# FMC_HPC_Connector.net
KiCad netlist of a schematic drawn in Altium Designer
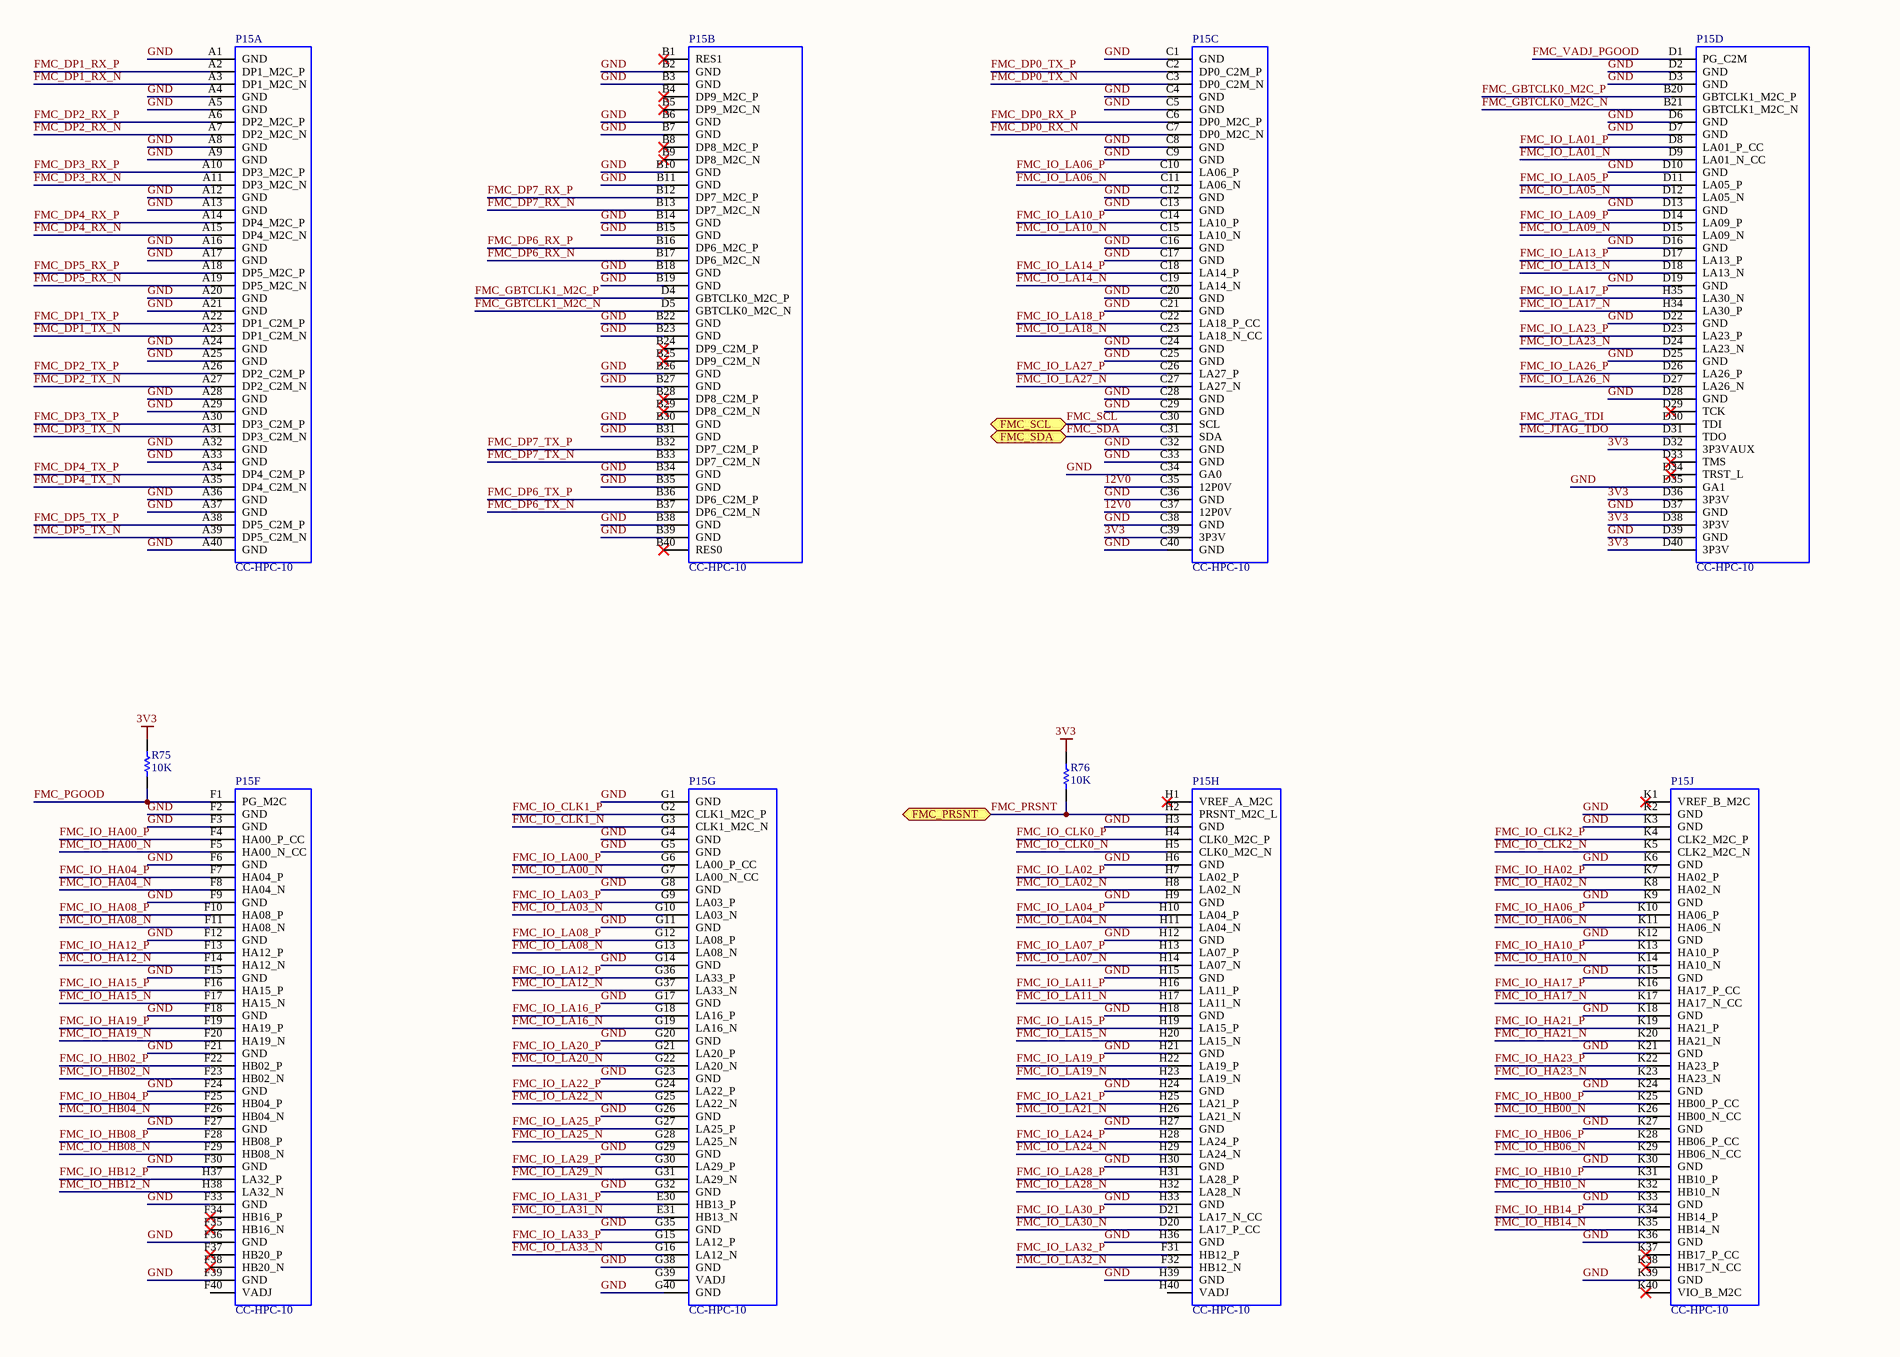
[diagram p0: FMC HPC Connector.SchDoc, top left]
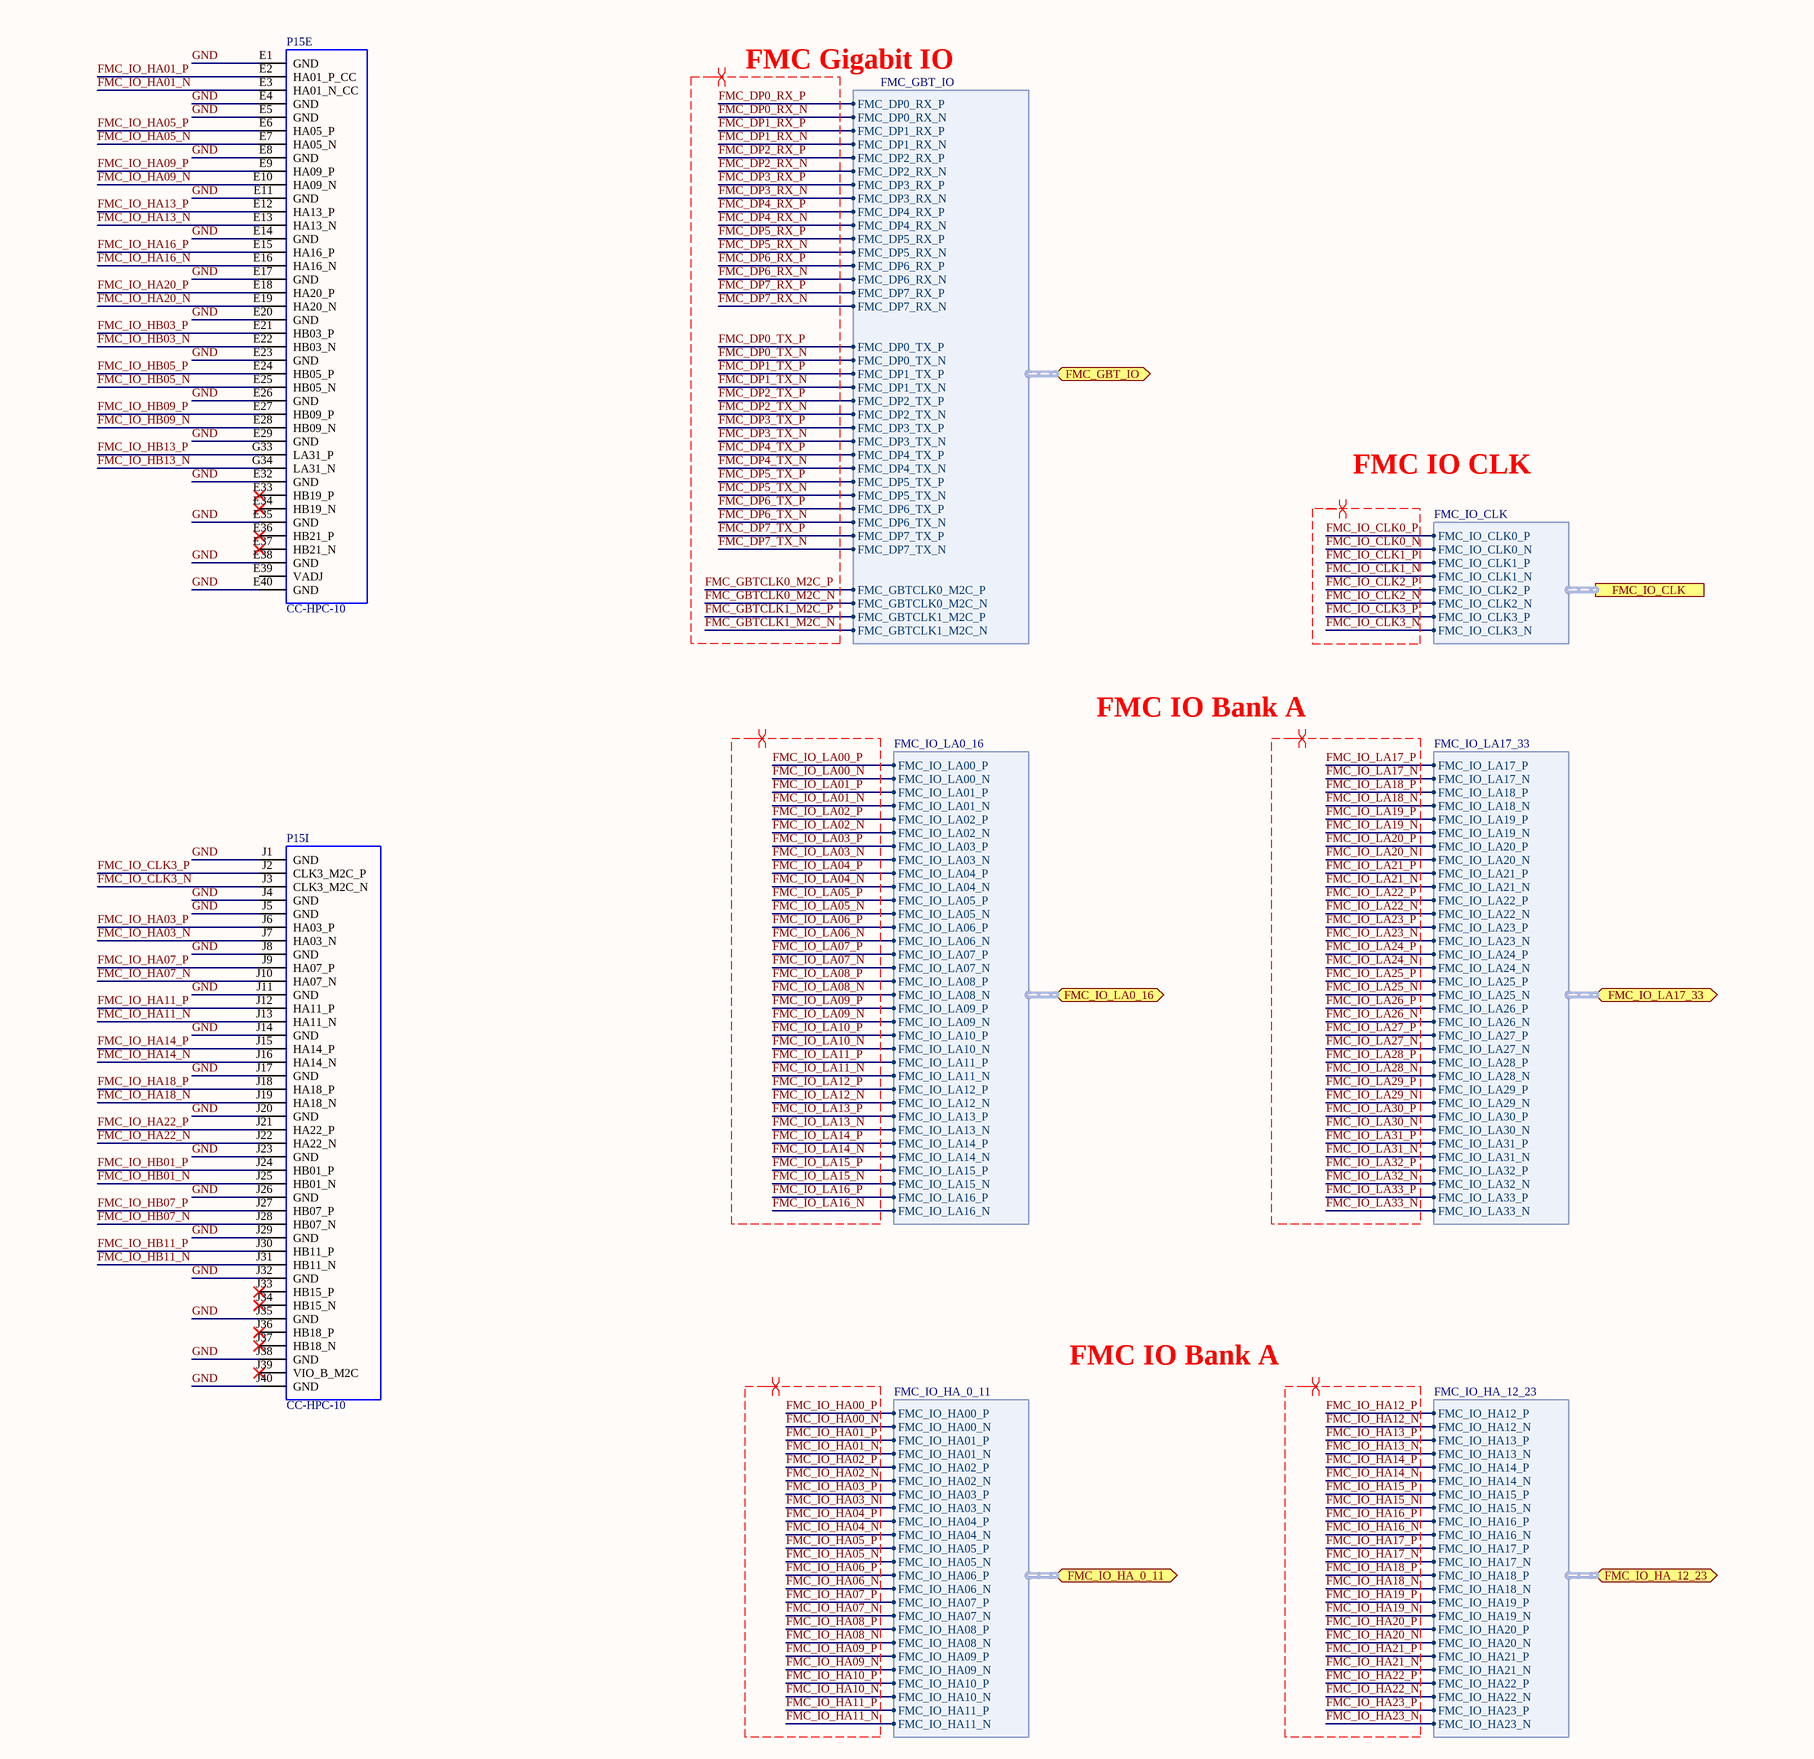
[diagram p1: FMC HPC Connector.SchDoc, top right]
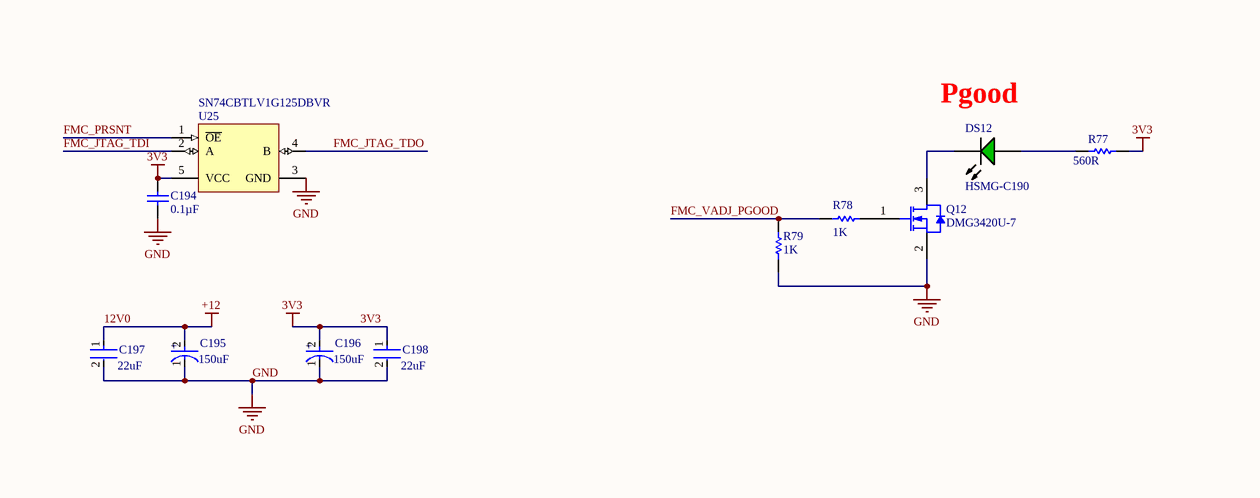
[diagram p2: FMC HPC Connector.SchDoc, bottom left]
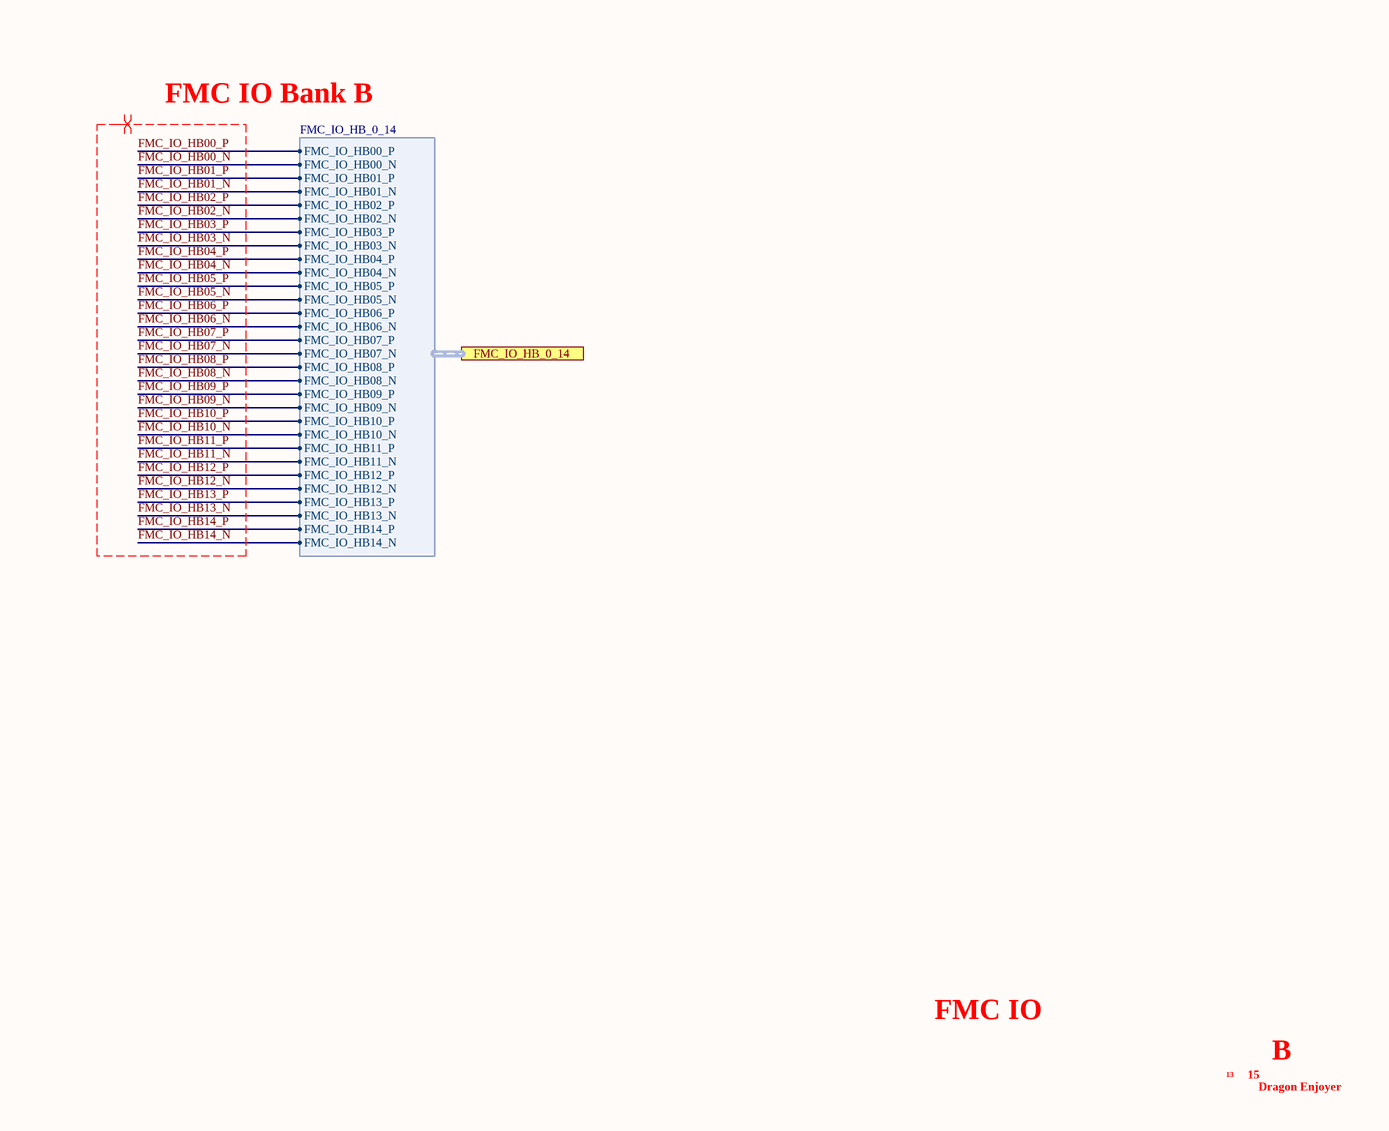
[diagram p3: FMC HPC Connector.SchDoc, bottom right]

(export (version "E")
  (design (tool "Eeschema 10.0.6"))
  (components
    (comp (ref "C194")
      (value "CC0402ZRY5V8BB104")
      (footprint "CAPC1005X55X25LL05T05")
      (description "Chip Capacitor, 100 nF, -20% to 80%, 25 V, -30 to 85 degC, 0402 (1005 Metric), RoHS, Tape and Reel")
      (fields
        (field (name "TOLERANCE") "-20%,+80%")
        (field (name "CAPACITANCE") "0.1µF")
        (field (name "MANUFACTURER") "Yageo")
      )
      (libsource (lib "Altium Content Vault") (part "CAP-NP-2"))
    )
    (comp (ref "C195")
      (value "TAJV157M025RNJ")
      (footprint "FP-TAJV-MFG")
      (description "150uF 25V  ±20% 400mΩ 2924  SMD Tantalum Capacitor")
      (fields (field (name "TOLERANCE") "20%") (field (name "CAPACITANCE") "150uF"))
      (libsource (lib "Altium Content Vault") (part "a00bbbee19879c290e62620ae7e47b1"))
    )
    (comp (ref "C196")
      (value "TAJV157M025RNJ")
      (footprint "FP-TAJV-MFG")
      (description "150uF 25V  ±20% 400mΩ 2924  SMD Tantalum Capacitor")
      (fields (field (name "TOLERANCE") "20%") (field (name "CAPACITANCE") "150uF"))
      (libsource (lib "Altium Content Vault") (part "a00bbbee19879c290e62620ae7e47b1"))
    )
    (comp (ref "C197")
      (value "22uF")
      (footprint "FP-CL31H-0_2-MFG")
      (description "CAP CER 22UF 25V X5R 1206")
      (fields
        (field (name "OCTOPART") "https://octopart.com/cl31a226kahnnne-samsung-19832795")
        (field (name "TOLERANCE") "10%")
      )
      (libsource (lib "Altium Content Vault") (part "11868f565c42a9108669ba33697ecf6"))
    )
    (comp (ref "C198")
      (value "22uF")
      (footprint "FP-CL31H-0_2-MFG")
      (description "CAP CER 22UF 25V X5R 1206")
      (fields
        (field (name "OCTOPART") "https://octopart.com/cl31a226kahnnne-samsung-19832795")
        (field (name "TOLERANCE") "10%")
      )
      (libsource (lib "Altium Content Vault") (part "11868f565c42a9108669ba33697ecf6"))
    )
    (comp (ref "DS12")
      (value "HSMG-C190")
      (footprint "AVAG-HSMX-C190_V")
      (description "Chip LED, Green, 2.2 V, -40 to 85 degC, 2-Pin SMD, RoHS, Tape and Reel")
      (libsource (lib "Altium Content Vault") (part "LED-GREEN-AK-2"))
    )
    (comp (ref "P15")
      (value "CC-HPC-10")
      (footprint "ASP-134486-01")
      (description "CC-HPC-10, FMC High-pin count connector, lead free, 400 I/Os, female, 10 mm mated stack height")
      (fields
        (field (name "PART") "ASP-134486-01")
        (field (name "MANUFACTURER") "Samtec")
        (field (name "SOURCE") "VITA_57_FMC.SchLib")
      )
      (libsource (lib "") (part "MC-HPC-10_5"))
    )
    (comp (ref "Q12")
      (value "DMG3420U-7")
      (footprint "DIOD-SOT23-3_B_V")
      (description "N-Channel Enhancement Mode MOSFET, 20 V, -55 to 150 degC, 3-Pin SOT23, RoHS, Tape and Reel")
      (fields (field (name "MANUFACTURER") "Diodes Inc"))
      (libsource (lib "Altium Content Vault") (part "NEMOS-GSD-3"))
    )
    (comp (ref "R75")
      (value "10K")
      (footprint "RESC1005X40X25NL05T05")
      (fields (field (name "MANUFACTURER") "Vishay Dale") (field (name "PART NUMBER") "CRCW040210K0JNED"))
      (libsource (lib "Altium Content Vault") (part "RES"))
    )
    (comp (ref "R76")
      (value "10K")
      (footprint "RESC1005X40X25NL05T05")
      (fields (field (name "MANUFACTURER") "Vishay Dale") (field (name "PART NUMBER") "CRCW040210K0JNED"))
      (libsource (lib "Altium Content Vault") (part "RES"))
    )
    (comp (ref "R77")
      (value "560R")
      (footprint "RESC1608X55X30LL20T20")
      (fields (field (name "PART NUMBER") "ERA3AEB561V") (field (name "MANUFACTURER") "Panasonic"))
      (libsource (lib "Altium Content Vault") (part "RES"))
    )
    (comp (ref "R78")
      (value "1K")
      (footprint "RESC1005X40X25NL05T10")
      (fields (field (name "PART NUMBER") "RC0402FR-071KL") (field (name "MANUFACTURER") "Yageo / Phycomp"))
      (libsource (lib "Altium Content Vault") (part "RES"))
    )
    (comp (ref "R79")
      (value "1K")
      (footprint "RESC1005X40X25NL05T10")
      (fields (field (name "PART NUMBER") "RC0402FR-071KL") (field (name "MANUFACTURER") "Yageo / Phycomp"))
      (libsource (lib "Altium Content Vault") (part "RES"))
    )
    (comp (ref "U25")
      (value "SN74CBTLV1G125DBVR")
      (footprint "DBV0005A_N")
      (description "Low-Voltage Single FET Bus Switch, DBV0005A, LARGE T&R")
      (fields
        (field (name "MANUFACTURER") "Texas Instruments")
        (field (name "GENERIC PART NUMBER") "SN74CBTLV1G125")
      )
      (libsource (lib "Altium Content Vault") (part "TI-SN74CBXTXX1G125-5"))
    )
  )
  (nets
    (net (code "8") (name "+12") (class "Default")
      (node (ref "C195") (pin "2") (pinfunction "A_2") (pintype "passive"))
      (node (ref "C197") (pin "1") (pinfunction "1_1") (pintype "passive"))
      (node (ref "P15") (pin "C35") (pinfunction "12P0V_C35") (pintype "passive"))
      (node (ref "P15") (pin "C37") (pinfunction "12P0V_C37") (pintype "passive"))
    )
    (net (code "9") (name "/FMC_DP0_RX_N") (class "Default")
      (node (ref "P15") (pin "C7") (pinfunction "DP0_M2C_N_C7") (pintype "passive"))
    )
    (net (code "10") (name "/FMC_DP0_RX_P") (class "Default")
      (node (ref "P15") (pin "C6") (pinfunction "DP0_M2C_P_C6") (pintype "passive"))
    )
    (net (code "11") (name "/FMC_DP0_TX_N") (class "Default")
      (node (ref "P15") (pin "C3") (pinfunction "DP0_C2M_N_C3") (pintype "passive"))
    )
    (net (code "12") (name "/FMC_DP0_TX_P") (class "Default")
      (node (ref "P15") (pin "C2") (pinfunction "DP0_C2M_P_C2") (pintype "passive"))
    )
    (net (code "13") (name "/FMC_DP1_RX_N") (class "Default")
      (node (ref "P15") (pin "A3") (pinfunction "DP1_M2C_N_A3") (pintype "passive"))
    )
    (net (code "14") (name "/FMC_DP1_RX_P") (class "Default")
      (node (ref "P15") (pin "A2") (pinfunction "DP1_M2C_P_A2") (pintype "passive"))
    )
    (net (code "15") (name "/FMC_DP1_TX_N") (class "Default")
      (node (ref "P15") (pin "A23") (pinfunction "DP1_C2M_N_A23") (pintype "passive"))
    )
    (net (code "16") (name "/FMC_DP1_TX_P") (class "Default")
      (node (ref "P15") (pin "A22") (pinfunction "DP1_C2M_P_A22") (pintype "passive"))
    )
    (net (code "17") (name "/FMC_DP2_RX_N") (class "Default")
      (node (ref "P15") (pin "A7") (pinfunction "DP2_M2C_N_A7") (pintype "passive"))
    )
    (net (code "18") (name "/FMC_DP2_RX_P") (class "Default")
      (node (ref "P15") (pin "A6") (pinfunction "DP2_M2C_P_A6") (pintype "passive"))
    )
    (net (code "19") (name "/FMC_DP2_TX_N") (class "Default")
      (node (ref "P15") (pin "A27") (pinfunction "DP2_C2M_N_A27") (pintype "passive"))
    )
    (net (code "20") (name "/FMC_DP2_TX_P") (class "Default")
      (node (ref "P15") (pin "A26") (pinfunction "DP2_C2M_P_A26") (pintype "passive"))
    )
    (net (code "21") (name "/FMC_DP3_RX_N") (class "Default")
      (node (ref "P15") (pin "A11") (pinfunction "DP3_M2C_N_A11") (pintype "passive"))
    )
    (net (code "22") (name "/FMC_DP3_RX_P") (class "Default")
      (node (ref "P15") (pin "A10") (pinfunction "DP3_M2C_P_A10") (pintype "passive"))
    )
    (net (code "23") (name "/FMC_DP3_TX_N") (class "Default")
      (node (ref "P15") (pin "A31") (pinfunction "DP3_C2M_N_A31") (pintype "passive"))
    )
    (net (code "24") (name "/FMC_DP3_TX_P") (class "Default")
      (node (ref "P15") (pin "A30") (pinfunction "DP3_C2M_P_A30") (pintype "passive"))
    )
    (net (code "25") (name "/FMC_DP4_RX_N") (class "Default")
      (node (ref "P15") (pin "A15") (pinfunction "DP4_M2C_N_A15") (pintype "passive"))
    )
    (net (code "26") (name "/FMC_DP4_RX_P") (class "Default")
      (node (ref "P15") (pin "A14") (pinfunction "DP4_M2C_P_A14") (pintype "passive"))
    )
    (net (code "27") (name "/FMC_DP4_TX_N") (class "Default")
      (node (ref "P15") (pin "A35") (pinfunction "DP4_C2M_N_A35") (pintype "passive"))
    )
    (net (code "28") (name "/FMC_DP4_TX_P") (class "Default")
      (node (ref "P15") (pin "A34") (pinfunction "DP4_C2M_P_A34") (pintype "passive"))
    )
    (net (code "29") (name "/FMC_DP5_RX_N") (class "Default")
      (node (ref "P15") (pin "A19") (pinfunction "DP5_M2C_N_A19") (pintype "passive"))
    )
    (net (code "30") (name "/FMC_DP5_RX_P") (class "Default")
      (node (ref "P15") (pin "A18") (pinfunction "DP5_M2C_P_A18") (pintype "passive"))
    )
    (net (code "31") (name "/FMC_DP5_TX_N") (class "Default")
      (node (ref "P15") (pin "A39") (pinfunction "DP5_C2M_N_A39") (pintype "passive"))
    )
    (net (code "32") (name "/FMC_DP5_TX_P") (class "Default")
      (node (ref "P15") (pin "A38") (pinfunction "DP5_C2M_P_A38") (pintype "passive"))
    )
    (net (code "33") (name "/FMC_DP6_RX_N") (class "Default")
      (node (ref "P15") (pin "B17") (pinfunction "DP6_M2C_N_B17") (pintype "passive"))
    )
    (net (code "34") (name "/FMC_DP6_RX_P") (class "Default")
      (node (ref "P15") (pin "B16") (pinfunction "DP6_M2C_P_B16") (pintype "passive"))
    )
    (net (code "35") (name "/FMC_DP6_TX_N") (class "Default")
      (node (ref "P15") (pin "B37") (pinfunction "DP6_C2M_N_B37") (pintype "passive"))
    )
    (net (code "36") (name "/FMC_DP6_TX_P") (class "Default")
      (node (ref "P15") (pin "B36") (pinfunction "DP6_C2M_P_B36") (pintype "passive"))
    )
    (net (code "37") (name "/FMC_DP7_RX_N") (class "Default")
      (node (ref "P15") (pin "B13") (pinfunction "DP7_M2C_N_B13") (pintype "passive"))
    )
    (net (code "38") (name "/FMC_DP7_RX_P") (class "Default")
      (node (ref "P15") (pin "B12") (pinfunction "DP7_M2C_P_B12") (pintype "passive"))
    )
    (net (code "39") (name "/FMC_DP7_TX_N") (class "Default")
      (node (ref "P15") (pin "B33") (pinfunction "DP7_C2M_N_B33") (pintype "passive"))
    )
    (net (code "40") (name "/FMC_DP7_TX_P") (class "Default")
      (node (ref "P15") (pin "B32") (pinfunction "DP7_C2M_P_B32") (pintype "passive"))
    )
    (net (code "41") (name "/FMC_GBTCLK0_M2C_N") (class "Default")
      (node (ref "P15") (pin "B21") (pinfunction "GBTCLK1_M2C_N_B21") (pintype "passive"))
    )
    (net (code "42") (name "/FMC_GBTCLK0_M2C_P") (class "Default")
      (node (ref "P15") (pin "B20") (pinfunction "GBTCLK1_M2C_P_B20") (pintype "passive"))
    )
    (net (code "43") (name "/FMC_GBTCLK1_M2C_N") (class "Default")
      (node (ref "P15") (pin "D5") (pinfunction "GBTCLK0_M2C_N_D5") (pintype "passive"))
    )
    (net (code "44") (name "/FMC_GBTCLK1_M2C_P") (class "Default")
      (node (ref "P15") (pin "D4") (pinfunction "GBTCLK0_M2C_P_D4") (pintype "passive"))
    )
    (net (code "45") (name "/FMC_IO_CLK0_N") (class "Default")
      (node (ref "P15") (pin "H5") (pinfunction "CLK0_M2C_N_H5") (pintype "passive"))
    )
    (net (code "46") (name "/FMC_IO_CLK0_P") (class "Default")
      (node (ref "P15") (pin "H4") (pinfunction "CLK0_M2C_P_H4") (pintype "passive"))
    )
    (net (code "47") (name "/FMC_IO_CLK1_N") (class "Default")
      (node (ref "P15") (pin "G3") (pinfunction "CLK1_M2C_N_G3") (pintype "passive"))
    )
    (net (code "48") (name "/FMC_IO_CLK1_P") (class "Default")
      (node (ref "P15") (pin "G2") (pinfunction "CLK1_M2C_P_G2") (pintype "passive"))
    )
    (net (code "49") (name "/FMC_IO_CLK2_N") (class "Default")
      (node (ref "P15") (pin "K5") (pinfunction "CLK2_M2C_N_K5") (pintype "passive"))
    )
    (net (code "50") (name "/FMC_IO_CLK2_P") (class "Default")
      (node (ref "P15") (pin "K4") (pinfunction "CLK2_M2C_P_K4") (pintype "passive"))
    )
    (net (code "51") (name "/FMC_IO_CLK3_N") (class "Default")
      (node (ref "P15") (pin "J3") (pinfunction "CLK3_M2C_N_J3") (pintype "passive"))
    )
    (net (code "52") (name "/FMC_IO_CLK3_P") (class "Default")
      (node (ref "P15") (pin "J2") (pinfunction "CLK3_M2C_P_J2") (pintype "passive"))
    )
    (net (code "53") (name "/FMC_IO_HA00_N") (class "Default")
      (node (ref "P15") (pin "F5") (pinfunction "HA00_N_CC_F5") (pintype "passive"))
    )
    (net (code "54") (name "/FMC_IO_HA00_P") (class "Default")
      (node (ref "P15") (pin "F4") (pinfunction "HA00_P_CC_F4") (pintype "passive"))
    )
    (net (code "55") (name "/FMC_IO_HA01_N") (class "Default")
      (node (ref "P15") (pin "E3") (pinfunction "HA01_N_CC_E3") (pintype "passive"))
    )
    (net (code "56") (name "/FMC_IO_HA01_P") (class "Default")
      (node (ref "P15") (pin "E2") (pinfunction "HA01_P_CC_E2") (pintype "passive"))
    )
    (net (code "57") (name "/FMC_IO_HA02_N") (class "Default")
      (node (ref "P15") (pin "K8") (pinfunction "HA02_N_K8") (pintype "passive"))
    )
    (net (code "58") (name "/FMC_IO_HA02_P") (class "Default")
      (node (ref "P15") (pin "K7") (pinfunction "HA02_P_K7") (pintype "passive"))
    )
    (net (code "59") (name "/FMC_IO_HA03_N") (class "Default")
      (node (ref "P15") (pin "J7") (pinfunction "HA03_N_J7") (pintype "passive"))
    )
    (net (code "60") (name "/FMC_IO_HA03_P") (class "Default")
      (node (ref "P15") (pin "J6") (pinfunction "HA03_P_J6") (pintype "passive"))
    )
    (net (code "61") (name "/FMC_IO_HA04_N") (class "Default")
      (node (ref "P15") (pin "F8") (pinfunction "HA04_N_F8") (pintype "passive"))
    )
    (net (code "62") (name "/FMC_IO_HA04_P") (class "Default")
      (node (ref "P15") (pin "F7") (pinfunction "HA04_P_F7") (pintype "passive"))
    )
    (net (code "63") (name "/FMC_IO_HA05_N") (class "Default")
      (node (ref "P15") (pin "E7") (pinfunction "HA05_N_E7") (pintype "passive"))
    )
    (net (code "64") (name "/FMC_IO_HA05_P") (class "Default")
      (node (ref "P15") (pin "E6") (pinfunction "HA05_P_E6") (pintype "passive"))
    )
    (net (code "65") (name "/FMC_IO_HA06_N") (class "Default")
      (node (ref "P15") (pin "K11") (pinfunction "HA06_N_K11") (pintype "passive"))
    )
    (net (code "66") (name "/FMC_IO_HA06_P") (class "Default")
      (node (ref "P15") (pin "K10") (pinfunction "HA06_P_K10") (pintype "passive"))
    )
    (net (code "67") (name "/FMC_IO_HA07_N") (class "Default")
      (node (ref "P15") (pin "J10") (pinfunction "HA07_N_J10") (pintype "passive"))
    )
    (net (code "68") (name "/FMC_IO_HA07_P") (class "Default")
      (node (ref "P15") (pin "J9") (pinfunction "HA07_P_J9") (pintype "passive"))
    )
    (net (code "69") (name "/FMC_IO_HA08_N") (class "Default")
      (node (ref "P15") (pin "F11") (pinfunction "HA08_N_F11") (pintype "passive"))
    )
    (net (code "70") (name "/FMC_IO_HA08_P") (class "Default")
      (node (ref "P15") (pin "F10") (pinfunction "HA08_P_F10") (pintype "passive"))
    )
    (net (code "71") (name "/FMC_IO_HA09_N") (class "Default")
      (node (ref "P15") (pin "E10") (pinfunction "HA09_N_E10") (pintype "passive"))
    )
    (net (code "72") (name "/FMC_IO_HA09_P") (class "Default")
      (node (ref "P15") (pin "E9") (pinfunction "HA09_P_E9") (pintype "passive"))
    )
    (net (code "73") (name "/FMC_IO_HA10_N") (class "Default")
      (node (ref "P15") (pin "K14") (pinfunction "HA10_N_K14") (pintype "passive"))
    )
    (net (code "74") (name "/FMC_IO_HA10_P") (class "Default")
      (node (ref "P15") (pin "K13") (pinfunction "HA10_P_K13") (pintype "passive"))
    )
    (net (code "75") (name "/FMC_IO_HA11_N") (class "Default")
      (node (ref "P15") (pin "J13") (pinfunction "HA11_N_J13") (pintype "passive"))
    )
    (net (code "76") (name "/FMC_IO_HA11_P") (class "Default")
      (node (ref "P15") (pin "J12") (pinfunction "HA11_P_J12") (pintype "passive"))
    )
    (net (code "77") (name "/FMC_IO_HA12_N") (class "Default")
      (node (ref "P15") (pin "F14") (pinfunction "HA12_N_F14") (pintype "passive"))
    )
    (net (code "78") (name "/FMC_IO_HA12_P") (class "Default")
      (node (ref "P15") (pin "F13") (pinfunction "HA12_P_F13") (pintype "passive"))
    )
    (net (code "79") (name "/FMC_IO_HA13_N") (class "Default")
      (node (ref "P15") (pin "E13") (pinfunction "HA13_N_E13") (pintype "passive"))
    )
    (net (code "80") (name "/FMC_IO_HA13_P") (class "Default")
      (node (ref "P15") (pin "E12") (pinfunction "HA13_P_E12") (pintype "passive"))
    )
    (net (code "81") (name "/FMC_IO_HA14_N") (class "Default")
      (node (ref "P15") (pin "J16") (pinfunction "HA14_N_J16") (pintype "passive"))
    )
    (net (code "82") (name "/FMC_IO_HA14_P") (class "Default")
      (node (ref "P15") (pin "J15") (pinfunction "HA14_P_J15") (pintype "passive"))
    )
    (net (code "83") (name "/FMC_IO_HA15_N") (class "Default")
      (node (ref "P15") (pin "F17") (pinfunction "HA15_N_F17") (pintype "passive"))
    )
    (net (code "84") (name "/FMC_IO_HA15_P") (class "Default")
      (node (ref "P15") (pin "F16") (pinfunction "HA15_P_F16") (pintype "passive"))
    )
    (net (code "85") (name "/FMC_IO_HA16_N") (class "Default")
      (node (ref "P15") (pin "E16") (pinfunction "HA16_N_E16") (pintype "passive"))
    )
    (net (code "86") (name "/FMC_IO_HA16_P") (class "Default")
      (node (ref "P15") (pin "E15") (pinfunction "HA16_P_E15") (pintype "passive"))
    )
    (net (code "87") (name "/FMC_IO_HA17_N") (class "Default")
      (node (ref "P15") (pin "K17") (pinfunction "HA17_N_CC_K17") (pintype "passive"))
    )
    (net (code "88") (name "/FMC_IO_HA17_P") (class "Default")
      (node (ref "P15") (pin "K16") (pinfunction "HA17_P_CC_K16") (pintype "passive"))
    )
    (net (code "89") (name "/FMC_IO_HA18_N") (class "Default")
      (node (ref "P15") (pin "J19") (pinfunction "HA18_N_J19") (pintype "passive"))
    )
    (net (code "90") (name "/FMC_IO_HA18_P") (class "Default")
      (node (ref "P15") (pin "J18") (pinfunction "HA18_P_J18") (pintype "passive"))
    )
    (net (code "91") (name "/FMC_IO_HA19_N") (class "Default")
      (node (ref "P15") (pin "F20") (pinfunction "HA19_N_F20") (pintype "passive"))
    )
    (net (code "92") (name "/FMC_IO_HA19_P") (class "Default")
      (node (ref "P15") (pin "F19") (pinfunction "HA19_P_F19") (pintype "passive"))
    )
    (net (code "93") (name "/FMC_IO_HA20_N") (class "Default")
      (node (ref "P15") (pin "E19") (pinfunction "HA20_N_E19") (pintype "passive"))
    )
    (net (code "94") (name "/FMC_IO_HA20_P") (class "Default")
      (node (ref "P15") (pin "E18") (pinfunction "HA20_P_E18") (pintype "passive"))
    )
    (net (code "95") (name "/FMC_IO_HA21_N") (class "Default")
      (node (ref "P15") (pin "K20") (pinfunction "HA21_N_K20") (pintype "passive"))
    )
    (net (code "96") (name "/FMC_IO_HA21_P") (class "Default")
      (node (ref "P15") (pin "K19") (pinfunction "HA21_P_K19") (pintype "passive"))
    )
    (net (code "97") (name "/FMC_IO_HA22_N") (class "Default")
      (node (ref "P15") (pin "J22") (pinfunction "HA22_N_J22") (pintype "passive"))
    )
    (net (code "98") (name "/FMC_IO_HA22_P") (class "Default")
      (node (ref "P15") (pin "J21") (pinfunction "HA22_P_J21") (pintype "passive"))
    )
    (net (code "99") (name "/FMC_IO_HA23_N") (class "Default")
      (node (ref "P15") (pin "K23") (pinfunction "HA23_N_K23") (pintype "passive"))
    )
    (net (code "100") (name "/FMC_IO_HA23_P") (class "Default")
      (node (ref "P15") (pin "K22") (pinfunction "HA23_P_K22") (pintype "passive"))
    )
    (net (code "101") (name "/FMC_IO_HB00_N") (class "Default")
      (node (ref "P15") (pin "K26") (pinfunction "HB00_N_CC_K26") (pintype "passive"))
    )
    (net (code "102") (name "/FMC_IO_HB00_P") (class "Default")
      (node (ref "P15") (pin "K25") (pinfunction "HB00_P_CC_K25") (pintype "passive"))
    )
    (net (code "103") (name "/FMC_IO_HB01_N") (class "Default")
      (node (ref "P15") (pin "J25") (pinfunction "HB01_N_J25") (pintype "passive"))
    )
    (net (code "104") (name "/FMC_IO_HB01_P") (class "Default")
      (node (ref "P15") (pin "J24") (pinfunction "HB01_P_J24") (pintype "passive"))
    )
    (net (code "105") (name "/FMC_IO_HB02_N") (class "Default")
      (node (ref "P15") (pin "F23") (pinfunction "HB02_N_F23") (pintype "passive"))
    )
    (net (code "106") (name "/FMC_IO_HB02_P") (class "Default")
      (node (ref "P15") (pin "F22") (pinfunction "HB02_P_F22") (pintype "passive"))
    )
    (net (code "107") (name "/FMC_IO_HB03_N") (class "Default")
      (node (ref "P15") (pin "E22") (pinfunction "HB03_N_E22") (pintype "passive"))
    )
    (net (code "108") (name "/FMC_IO_HB03_P") (class "Default")
      (node (ref "P15") (pin "E21") (pinfunction "HB03_P_E21") (pintype "passive"))
    )
    (net (code "109") (name "/FMC_IO_HB04_N") (class "Default")
      (node (ref "P15") (pin "F26") (pinfunction "HB04_N_F26") (pintype "passive"))
    )
    (net (code "110") (name "/FMC_IO_HB04_P") (class "Default")
      (node (ref "P15") (pin "F25") (pinfunction "HB04_P_F25") (pintype "passive"))
    )
    (net (code "111") (name "/FMC_IO_HB05_N") (class "Default")
      (node (ref "P15") (pin "E25") (pinfunction "HB05_N_E25") (pintype "passive"))
    )
    (net (code "112") (name "/FMC_IO_HB05_P") (class "Default")
      (node (ref "P15") (pin "E24") (pinfunction "HB05_P_E24") (pintype "passive"))
    )
    (net (code "113") (name "/FMC_IO_HB06_N") (class "Default")
      (node (ref "P15") (pin "K29") (pinfunction "HB06_N_CC_K29") (pintype "passive"))
    )
    (net (code "114") (name "/FMC_IO_HB06_P") (class "Default")
      (node (ref "P15") (pin "K28") (pinfunction "HB06_P_CC_K28") (pintype "passive"))
    )
    (net (code "115") (name "/FMC_IO_HB07_N") (class "Default")
      (node (ref "P15") (pin "J28") (pinfunction "HB07_N_J28") (pintype "passive"))
    )
    (net (code "116") (name "/FMC_IO_HB07_P") (class "Default")
      (node (ref "P15") (pin "J27") (pinfunction "HB07_P_J27") (pintype "passive"))
    )
    (net (code "117") (name "/FMC_IO_HB08_N") (class "Default")
      (node (ref "P15") (pin "F29") (pinfunction "HB08_N_F29") (pintype "passive"))
    )
    (net (code "118") (name "/FMC_IO_HB08_P") (class "Default")
      (node (ref "P15") (pin "F28") (pinfunction "HB08_P_F28") (pintype "passive"))
    )
    (net (code "119") (name "/FMC_IO_HB09_N") (class "Default")
      (node (ref "P15") (pin "E28") (pinfunction "HB09_N_E28") (pintype "passive"))
    )
    (net (code "120") (name "/FMC_IO_HB09_P") (class "Default")
      (node (ref "P15") (pin "E27") (pinfunction "HB09_P_E27") (pintype "passive"))
    )
    (net (code "121") (name "/FMC_IO_HB10_N") (class "Default")
      (node (ref "P15") (pin "K32") (pinfunction "HB10_N_K32") (pintype "passive"))
    )
    (net (code "122") (name "/FMC_IO_HB10_P") (class "Default")
      (node (ref "P15") (pin "K31") (pinfunction "HB10_P_K31") (pintype "passive"))
    )
    (net (code "123") (name "/FMC_IO_HB11_N") (class "Default")
      (node (ref "P15") (pin "J31") (pinfunction "HB11_N_J31") (pintype "passive"))
    )
    (net (code "124") (name "/FMC_IO_HB11_P") (class "Default")
      (node (ref "P15") (pin "J30") (pinfunction "HB11_P_J30") (pintype "passive"))
    )
    (net (code "125") (name "/FMC_IO_HB12_N") (class "Default")
      (node (ref "P15") (pin "H38") (pinfunction "LA32_N_H38") (pintype "passive"))
    )
    (net (code "126") (name "/FMC_IO_HB12_P") (class "Default")
      (node (ref "P15") (pin "H37") (pinfunction "LA32_P_H37") (pintype "passive"))
    )
    (net (code "127") (name "/FMC_IO_HB13_N") (class "Default")
      (node (ref "P15") (pin "G34") (pinfunction "LA31_N_G34") (pintype "passive"))
    )
    (net (code "128") (name "/FMC_IO_HB13_P") (class "Default")
      (node (ref "P15") (pin "G33") (pinfunction "LA31_P_G33") (pintype "passive"))
    )
    (net (code "129") (name "/FMC_IO_HB14_N") (class "Default")
      (node (ref "P15") (pin "K35") (pinfunction "HB14_N_K35") (pintype "passive"))
    )
    (net (code "130") (name "/FMC_IO_HB14_P") (class "Default")
      (node (ref "P15") (pin "K34") (pinfunction "HB14_P_K34") (pintype "passive"))
    )
    (net (code "131") (name "/FMC_IO_LA00_N") (class "Default")
      (node (ref "P15") (pin "G7") (pinfunction "LA00_N_CC_G7") (pintype "passive"))
    )
    (net (code "132") (name "/FMC_IO_LA00_P") (class "Default")
      (node (ref "P15") (pin "G6") (pinfunction "LA00_P_CC_G6") (pintype "passive"))
    )
    (net (code "133") (name "/FMC_IO_LA01_N") (class "Default")
      (node (ref "P15") (pin "D9") (pinfunction "LA01_N_CC_D9") (pintype "passive"))
    )
    (net (code "134") (name "/FMC_IO_LA01_P") (class "Default")
      (node (ref "P15") (pin "D8") (pinfunction "LA01_P_CC_D8") (pintype "passive"))
    )
    (net (code "135") (name "/FMC_IO_LA02_N") (class "Default")
      (node (ref "P15") (pin "H8") (pinfunction "LA02_N_H8") (pintype "passive"))
    )
    (net (code "136") (name "/FMC_IO_LA02_P") (class "Default")
      (node (ref "P15") (pin "H7") (pinfunction "LA02_P_H7") (pintype "passive"))
    )
    (net (code "137") (name "/FMC_IO_LA03_N") (class "Default")
      (node (ref "P15") (pin "G10") (pinfunction "LA03_N_G10") (pintype "passive"))
    )
    (net (code "138") (name "/FMC_IO_LA03_P") (class "Default")
      (node (ref "P15") (pin "G9") (pinfunction "LA03_P_G9") (pintype "passive"))
    )
    (net (code "139") (name "/FMC_IO_LA04_N") (class "Default")
      (node (ref "P15") (pin "H11") (pinfunction "LA04_N_H11") (pintype "passive"))
    )
    (net (code "140") (name "/FMC_IO_LA04_P") (class "Default")
      (node (ref "P15") (pin "H10") (pinfunction "LA04_P_H10") (pintype "passive"))
    )
    (net (code "141") (name "/FMC_IO_LA05_N") (class "Default")
      (node (ref "P15") (pin "D12") (pinfunction "LA05_N_D12") (pintype "passive"))
    )
    (net (code "142") (name "/FMC_IO_LA05_P") (class "Default")
      (node (ref "P15") (pin "D11") (pinfunction "LA05_P_D11") (pintype "passive"))
    )
    (net (code "143") (name "/FMC_IO_LA06_N") (class "Default")
      (node (ref "P15") (pin "C11") (pinfunction "LA06_N_C11") (pintype "passive"))
    )
    (net (code "144") (name "/FMC_IO_LA06_P") (class "Default")
      (node (ref "P15") (pin "C10") (pinfunction "LA06_P_C10") (pintype "passive"))
    )
    (net (code "145") (name "/FMC_IO_LA07_N") (class "Default")
      (node (ref "P15") (pin "H14") (pinfunction "LA07_N_H14") (pintype "passive"))
    )
    (net (code "146") (name "/FMC_IO_LA07_P") (class "Default")
      (node (ref "P15") (pin "H13") (pinfunction "LA07_P_H13") (pintype "passive"))
    )
    (net (code "147") (name "/FMC_IO_LA08_N") (class "Default")
      (node (ref "P15") (pin "G13") (pinfunction "LA08_N_G13") (pintype "passive"))
    )
    (net (code "148") (name "/FMC_IO_LA08_P") (class "Default")
      (node (ref "P15") (pin "G12") (pinfunction "LA08_P_G12") (pintype "passive"))
    )
    (net (code "149") (name "/FMC_IO_LA09_N") (class "Default")
      (node (ref "P15") (pin "D15") (pinfunction "LA09_N_D15") (pintype "passive"))
    )
    (net (code "150") (name "/FMC_IO_LA09_P") (class "Default")
      (node (ref "P15") (pin "D14") (pinfunction "LA09_P_D14") (pintype "passive"))
    )
    (net (code "151") (name "/FMC_IO_LA10_N") (class "Default")
      (node (ref "P15") (pin "C15") (pinfunction "LA10_N_C15") (pintype "passive"))
    )
    (net (code "152") (name "/FMC_IO_LA10_P") (class "Default")
      (node (ref "P15") (pin "C14") (pinfunction "LA10_P_C14") (pintype "passive"))
    )
    (net (code "153") (name "/FMC_IO_LA11_N") (class "Default")
      (node (ref "P15") (pin "H17") (pinfunction "LA11_N_H17") (pintype "passive"))
    )
    (net (code "154") (name "/FMC_IO_LA11_P") (class "Default")
      (node (ref "P15") (pin "H16") (pinfunction "LA11_P_H16") (pintype "passive"))
    )
    (net (code "155") (name "/FMC_IO_LA12_N") (class "Default")
      (node (ref "P15") (pin "G37") (pinfunction "LA33_N_G37") (pintype "passive"))
    )
    (net (code "156") (name "/FMC_IO_LA12_P") (class "Default")
      (node (ref "P15") (pin "G36") (pinfunction "LA33_P_G36") (pintype "passive"))
    )
    (net (code "157") (name "/FMC_IO_LA13_N") (class "Default")
      (node (ref "P15") (pin "D18") (pinfunction "LA13_N_D18") (pintype "passive"))
    )
    (net (code "158") (name "/FMC_IO_LA13_P") (class "Default")
      (node (ref "P15") (pin "D17") (pinfunction "LA13_P_D17") (pintype "passive"))
    )
    (net (code "159") (name "/FMC_IO_LA14_N") (class "Default")
      (node (ref "P15") (pin "C19") (pinfunction "LA14_N_C19") (pintype "passive"))
    )
    (net (code "160") (name "/FMC_IO_LA14_P") (class "Default")
      (node (ref "P15") (pin "C18") (pinfunction "LA14_P_C18") (pintype "passive"))
    )
    (net (code "161") (name "/FMC_IO_LA15_N") (class "Default")
      (node (ref "P15") (pin "H20") (pinfunction "LA15_N_H20") (pintype "passive"))
    )
    (net (code "162") (name "/FMC_IO_LA15_P") (class "Default")
      (node (ref "P15") (pin "H19") (pinfunction "LA15_P_H19") (pintype "passive"))
    )
    (net (code "163") (name "/FMC_IO_LA16_N") (class "Default")
      (node (ref "P15") (pin "G19") (pinfunction "LA16_N_G19") (pintype "passive"))
    )
    (net (code "164") (name "/FMC_IO_LA16_P") (class "Default")
      (node (ref "P15") (pin "G18") (pinfunction "LA16_P_G18") (pintype "passive"))
    )
    (net (code "165") (name "/FMC_IO_LA17_N") (class "Default")
      (node (ref "P15") (pin "H34") (pinfunction "LA30_P_H34") (pintype "passive"))
    )
    (net (code "166") (name "/FMC_IO_LA17_P") (class "Default")
      (node (ref "P15") (pin "H35") (pinfunction "LA30_N_H35") (pintype "passive"))
    )
    (net (code "167") (name "/FMC_IO_LA18_N") (class "Default")
      (node (ref "P15") (pin "C23") (pinfunction "LA18_N_CC_C23") (pintype "passive"))
    )
    (net (code "168") (name "/FMC_IO_LA18_P") (class "Default")
      (node (ref "P15") (pin "C22") (pinfunction "LA18_P_CC_C22") (pintype "passive"))
    )
    (net (code "169") (name "/FMC_IO_LA19_N") (class "Default")
      (node (ref "P15") (pin "H23") (pinfunction "LA19_N_H23") (pintype "passive"))
    )
    (net (code "170") (name "/FMC_IO_LA19_P") (class "Default")
      (node (ref "P15") (pin "H22") (pinfunction "LA19_P_H22") (pintype "passive"))
    )
    (net (code "171") (name "/FMC_IO_LA20_N") (class "Default")
      (node (ref "P15") (pin "G22") (pinfunction "LA20_N_G22") (pintype "passive"))
    )
    (net (code "172") (name "/FMC_IO_LA20_P") (class "Default")
      (node (ref "P15") (pin "G21") (pinfunction "LA20_P_G21") (pintype "passive"))
    )
    (net (code "173") (name "/FMC_IO_LA21_N") (class "Default")
      (node (ref "P15") (pin "H26") (pinfunction "LA21_N_H26") (pintype "passive"))
    )
    (net (code "174") (name "/FMC_IO_LA21_P") (class "Default")
      (node (ref "P15") (pin "H25") (pinfunction "LA21_P_H25") (pintype "passive"))
    )
    (net (code "175") (name "/FMC_IO_LA22_N") (class "Default")
      (node (ref "P15") (pin "G25") (pinfunction "LA22_N_G25") (pintype "passive"))
    )
    (net (code "176") (name "/FMC_IO_LA22_P") (class "Default")
      (node (ref "P15") (pin "G24") (pinfunction "LA22_P_G24") (pintype "passive"))
    )
    (net (code "177") (name "/FMC_IO_LA23_N") (class "Default")
      (node (ref "P15") (pin "D24") (pinfunction "LA23_N_D24") (pintype "passive"))
    )
    (net (code "178") (name "/FMC_IO_LA23_P") (class "Default")
      (node (ref "P15") (pin "D23") (pinfunction "LA23_P_D23") (pintype "passive"))
    )
    (net (code "179") (name "/FMC_IO_LA24_N") (class "Default")
      (node (ref "P15") (pin "H29") (pinfunction "LA24_N_H29") (pintype "passive"))
    )
    (net (code "180") (name "/FMC_IO_LA24_P") (class "Default")
      (node (ref "P15") (pin "H28") (pinfunction "LA24_P_H28") (pintype "passive"))
    )
    (net (code "181") (name "/FMC_IO_LA25_N") (class "Default")
      (node (ref "P15") (pin "G28") (pinfunction "LA25_N_G28") (pintype "passive"))
    )
    (net (code "182") (name "/FMC_IO_LA25_P") (class "Default")
      (node (ref "P15") (pin "G27") (pinfunction "LA25_P_G27") (pintype "passive"))
    )
    (net (code "183") (name "/FMC_IO_LA26_N") (class "Default")
      (node (ref "P15") (pin "D27") (pinfunction "LA26_N_D27") (pintype "passive"))
    )
    (net (code "184") (name "/FMC_IO_LA26_P") (class "Default")
      (node (ref "P15") (pin "D26") (pinfunction "LA26_P_D26") (pintype "passive"))
    )
    (net (code "185") (name "/FMC_IO_LA27_N") (class "Default")
      (node (ref "P15") (pin "C27") (pinfunction "LA27_N_C27") (pintype "passive"))
    )
    (net (code "186") (name "/FMC_IO_LA27_P") (class "Default")
      (node (ref "P15") (pin "C26") (pinfunction "LA27_P_C26") (pintype "passive"))
    )
    (net (code "187") (name "/FMC_IO_LA28_N") (class "Default")
      (node (ref "P15") (pin "H32") (pinfunction "LA28_N_H32") (pintype "passive"))
    )
    (net (code "188") (name "/FMC_IO_LA28_P") (class "Default")
      (node (ref "P15") (pin "H31") (pinfunction "LA28_P_H31") (pintype "passive"))
    )
    (net (code "189") (name "/FMC_IO_LA29_N") (class "Default")
      (node (ref "P15") (pin "G31") (pinfunction "LA29_N_G31") (pintype "passive"))
    )
    (net (code "190") (name "/FMC_IO_LA29_P") (class "Default")
      (node (ref "P15") (pin "G30") (pinfunction "LA29_P_G30") (pintype "passive"))
    )
    (net (code "191") (name "/FMC_IO_LA30_N") (class "Default")
      (node (ref "P15") (pin "D20") (pinfunction "LA17_P_CC_D20") (pintype "passive"))
    )
    (net (code "192") (name "/FMC_IO_LA30_P") (class "Default")
      (node (ref "P15") (pin "D21") (pinfunction "LA17_N_CC_D21") (pintype "passive"))
    )
    (net (code "193") (name "/FMC_IO_LA31_N") (class "Default")
      (node (ref "P15") (pin "E31") (pinfunction "HB13_N_E31") (pintype "passive"))
    )
    (net (code "194") (name "/FMC_IO_LA31_P") (class "Default")
      (node (ref "P15") (pin "E30") (pinfunction "HB13_P_E30") (pintype "passive"))
    )
    (net (code "195") (name "/FMC_IO_LA32_N") (class "Default")
      (node (ref "P15") (pin "F32") (pinfunction "HB12_N_F32") (pintype "passive"))
    )
    (net (code "196") (name "/FMC_IO_LA32_P") (class "Default")
      (node (ref "P15") (pin "F31") (pinfunction "HB12_P_F31") (pintype "passive"))
    )
    (net (code "197") (name "/FMC_IO_LA33_N") (class "Default")
      (node (ref "P15") (pin "G16") (pinfunction "LA12_N_G16") (pintype "passive"))
    )
    (net (code "198") (name "/FMC_IO_LA33_P") (class "Default")
      (node (ref "P15") (pin "G15") (pinfunction "LA12_P_G15") (pintype "passive"))
    )
    (net (code "199") (name "/FMC_JTAG_TDI") (class "Default")
      (node (ref "P15") (pin "D30") (pinfunction "TDI_D30") (pintype "passive"))
      (node (ref "U25") (pin "2") (pinfunction "A_2") (pintype "bidirectional"))
    )
    (net (code "200") (name "/FMC_JTAG_TDO") (class "Default")
      (node (ref "P15") (pin "D31") (pinfunction "TDO_D31") (pintype "passive"))
      (node (ref "U25") (pin "4") (pinfunction "B_4") (pintype "bidirectional"))
    )
    (net (code "201") (name "/FMC_PGOOD") (class "Default")
      (node (ref "P15") (pin "F1") (pinfunction "PG_M2C_F1") (pintype "passive"))
      (node (ref "R75") (pin "1") (pinfunction "1_1") (pintype "passive"))
    )
    (net (code "202") (name "/FMC_PRSNT") (class "Default")
      (node (ref "P15") (pin "H2") (pinfunction "PRSNT_M2C_L_H2") (pintype "passive"))
      (node (ref "R76") (pin "1") (pinfunction "1_1") (pintype "passive"))
      (node (ref "U25") (pin "1") (pinfunction "~{OE}_1") (pintype "input"))
    )
    (net (code "203") (name "/FMC_SCL") (class "Default")
      (node (ref "P15") (pin "C30") (pinfunction "SCL_C30") (pintype "passive"))
    )
    (net (code "204") (name "/FMC_SDA") (class "Default")
      (node (ref "P15") (pin "C31") (pinfunction "SDA_C31") (pintype "passive"))
    )
    (net (code "205") (name "/FMC_VADJ_PGOOD") (class "Default")
      (node (ref "P15") (pin "D1") (pinfunction "PG_C2M_D1") (pintype "passive"))
      (node (ref "R78") (pin "1") (pinfunction "1_1") (pintype "passive"))
      (node (ref "R79") (pin "2") (pinfunction "2_2") (pintype "passive"))
    )
    (net (code "213") (name "3V3") (class "Default")
      (node (ref "C194") (pin "2") (pinfunction "2_2") (pintype "passive"))
      (node (ref "C196") (pin "2") (pinfunction "A_2") (pintype "passive"))
      (node (ref "C198") (pin "1") (pinfunction "1_1") (pintype "passive"))
      (node (ref "P15") (pin "C39") (pinfunction "3P3V_C39") (pintype "passive"))
      (node (ref "P15") (pin "D32") (pinfunction "3P3VAUX_D32") (pintype "passive"))
      (node (ref "P15") (pin "D36") (pinfunction "3P3V_D36") (pintype "passive"))
      (node (ref "P15") (pin "D38") (pinfunction "3P3V_D38") (pintype "passive"))
      (node (ref "P15") (pin "D40") (pinfunction "3P3V_D40") (pintype "passive"))
      (node (ref "R75") (pin "2") (pinfunction "2_2") (pintype "passive"))
      (node (ref "R76") (pin "2") (pinfunction "2_2") (pintype "passive"))
      (node (ref "R77") (pin "2") (pinfunction "2_2") (pintype "passive"))
      (node (ref "U25") (pin "5") (pinfunction "VCC_5") (pintype "power_in"))
    )
    (net (code "214") (name "GND") (class "Default")
      (node (ref "C194") (pin "1") (pinfunction "1_1") (pintype "passive"))
      (node (ref "C195") (pin "1") (pinfunction "C_1") (pintype "passive"))
      (node (ref "C196") (pin "1") (pinfunction "C_1") (pintype "passive"))
      (node (ref "C197") (pin "2") (pinfunction "2_2") (pintype "passive"))
      (node (ref "C198") (pin "2") (pinfunction "2_2") (pintype "passive"))
      (node (ref "P15") (pin "A1") (pinfunction "GND_A1") (pintype "passive"))
      (node (ref "P15") (pin "A12") (pinfunction "GND_A12") (pintype "passive"))
      (node (ref "P15") (pin "A13") (pinfunction "GND_A13") (pintype "passive"))
      (node (ref "P15") (pin "A16") (pinfunction "GND_A16") (pintype "passive"))
      (node (ref "P15") (pin "A17") (pinfunction "GND_A17") (pintype "passive"))
      (node (ref "P15") (pin "A20") (pinfunction "GND_A20") (pintype "passive"))
      (node (ref "P15") (pin "A21") (pinfunction "GND_A21") (pintype "passive"))
      (node (ref "P15") (pin "A24") (pinfunction "GND_A24") (pintype "passive"))
      (node (ref "P15") (pin "A25") (pinfunction "GND_A25") (pintype "passive"))
      (node (ref "P15") (pin "A28") (pinfunction "GND_A28") (pintype "passive"))
      (node (ref "P15") (pin "A29") (pinfunction "GND_A29") (pintype "passive"))
      (node (ref "P15") (pin "A32") (pinfunction "GND_A32") (pintype "passive"))
      (node (ref "P15") (pin "A33") (pinfunction "GND_A33") (pintype "passive"))
      (node (ref "P15") (pin "A36") (pinfunction "GND_A36") (pintype "passive"))
      (node (ref "P15") (pin "A37") (pinfunction "GND_A37") (pintype "passive"))
      (node (ref "P15") (pin "A4") (pinfunction "GND_A4") (pintype "passive"))
      (node (ref "P15") (pin "A40") (pinfunction "GND_A40") (pintype "passive"))
      (node (ref "P15") (pin "A5") (pinfunction "GND_A5") (pintype "passive"))
      (node (ref "P15") (pin "A8") (pinfunction "GND_A8") (pintype "passive"))
      (node (ref "P15") (pin "A9") (pinfunction "GND_A9") (pintype "passive"))
      (node (ref "P15") (pin "B10") (pinfunction "GND_B10") (pintype "passive"))
      (node (ref "P15") (pin "B11") (pinfunction "GND_B11") (pintype "passive"))
      (node (ref "P15") (pin "B14") (pinfunction "GND_B14") (pintype "passive"))
      (node (ref "P15") (pin "B15") (pinfunction "GND_B15") (pintype "passive"))
      (node (ref "P15") (pin "B18") (pinfunction "GND_B18") (pintype "passive"))
      (node (ref "P15") (pin "B19") (pinfunction "GND_B19") (pintype "passive"))
      (node (ref "P15") (pin "B2") (pinfunction "GND_B2") (pintype "passive"))
      (node (ref "P15") (pin "B22") (pinfunction "GND_B22") (pintype "passive"))
      (node (ref "P15") (pin "B23") (pinfunction "GND_B23") (pintype "passive"))
      (node (ref "P15") (pin "B26") (pinfunction "GND_B26") (pintype "passive"))
      (node (ref "P15") (pin "B27") (pinfunction "GND_B27") (pintype "passive"))
      (node (ref "P15") (pin "B3") (pinfunction "GND_B3") (pintype "passive"))
      (node (ref "P15") (pin "B30") (pinfunction "GND_B30") (pintype "passive"))
      (node (ref "P15") (pin "B31") (pinfunction "GND_B31") (pintype "passive"))
      (node (ref "P15") (pin "B34") (pinfunction "GND_B34") (pintype "passive"))
      (node (ref "P15") (pin "B35") (pinfunction "GND_B35") (pintype "passive"))
      (node (ref "P15") (pin "B38") (pinfunction "GND_B38") (pintype "passive"))
      (node (ref "P15") (pin "B39") (pinfunction "GND_B39") (pintype "passive"))
      (node (ref "P15") (pin "B6") (pinfunction "GND_B6") (pintype "passive"))
      (node (ref "P15") (pin "B7") (pinfunction "GND_B7") (pintype "passive"))
      (node (ref "P15") (pin "C1") (pinfunction "GND_C1") (pintype "passive"))
      (node (ref "P15") (pin "C12") (pinfunction "GND_C12") (pintype "passive"))
      (node (ref "P15") (pin "C13") (pinfunction "GND_C13") (pintype "passive"))
      (node (ref "P15") (pin "C16") (pinfunction "GND_C16") (pintype "passive"))
      (node (ref "P15") (pin "C17") (pinfunction "GND_C17") (pintype "passive"))
      (node (ref "P15") (pin "C20") (pinfunction "GND_C20") (pintype "passive"))
      (node (ref "P15") (pin "C21") (pinfunction "GND_C21") (pintype "passive"))
      (node (ref "P15") (pin "C24") (pinfunction "GND_C24") (pintype "passive"))
      (node (ref "P15") (pin "C25") (pinfunction "GND_C25") (pintype "passive"))
      (node (ref "P15") (pin "C28") (pinfunction "GND_C28") (pintype "passive"))
      (node (ref "P15") (pin "C29") (pinfunction "GND_C29") (pintype "passive"))
      (node (ref "P15") (pin "C32") (pinfunction "GND_C32") (pintype "passive"))
      (node (ref "P15") (pin "C33") (pinfunction "GND_C33") (pintype "passive"))
      (node (ref "P15") (pin "C34") (pinfunction "GA0_C34") (pintype "passive"))
      (node (ref "P15") (pin "C36") (pinfunction "GND_C36") (pintype "passive"))
      (node (ref "P15") (pin "C38") (pinfunction "GND_C38") (pintype "passive"))
      (node (ref "P15") (pin "C4") (pinfunction "GND_C4") (pintype "passive"))
      (node (ref "P15") (pin "C40") (pinfunction "GND_C40") (pintype "passive"))
      (node (ref "P15") (pin "C5") (pinfunction "GND_C5") (pintype "passive"))
      (node (ref "P15") (pin "C8") (pinfunction "GND_C8") (pintype "passive"))
      (node (ref "P15") (pin "C9") (pinfunction "GND_C9") (pintype "passive"))
      (node (ref "P15") (pin "D10") (pinfunction "GND_D10") (pintype "passive"))
      (node (ref "P15") (pin "D13") (pinfunction "GND_D13") (pintype "passive"))
      (node (ref "P15") (pin "D16") (pinfunction "GND_D16") (pintype "passive"))
      (node (ref "P15") (pin "D19") (pinfunction "GND_D19") (pintype "passive"))
      (node (ref "P15") (pin "D2") (pinfunction "GND_D2") (pintype "passive"))
      (node (ref "P15") (pin "D22") (pinfunction "GND_D22") (pintype "passive"))
      (node (ref "P15") (pin "D25") (pinfunction "GND_D25") (pintype "passive"))
      (node (ref "P15") (pin "D28") (pinfunction "GND_D28") (pintype "passive"))
      (node (ref "P15") (pin "D3") (pinfunction "GND_D3") (pintype "passive"))
      (node (ref "P15") (pin "D35") (pinfunction "GA1_D35") (pintype "passive"))
      (node (ref "P15") (pin "D37") (pinfunction "GND_D37") (pintype "passive"))
      (node (ref "P15") (pin "D39") (pinfunction "GND_D39") (pintype "passive"))
      (node (ref "P15") (pin "D6") (pinfunction "GND_D6") (pintype "passive"))
      (node (ref "P15") (pin "D7") (pinfunction "GND_D7") (pintype "passive"))
      (node (ref "P15") (pin "E1") (pinfunction "GND_E1") (pintype "passive"))
      (node (ref "P15") (pin "E11") (pinfunction "GND_E11") (pintype "passive"))
      (node (ref "P15") (pin "E14") (pinfunction "GND_E14") (pintype "passive"))
      (node (ref "P15") (pin "E17") (pinfunction "GND_E17") (pintype "passive"))
      (node (ref "P15") (pin "E20") (pinfunction "GND_E20") (pintype "passive"))
      (node (ref "P15") (pin "E23") (pinfunction "GND_E23") (pintype "passive"))
      (node (ref "P15") (pin "E26") (pinfunction "GND_E26") (pintype "passive"))
      (node (ref "P15") (pin "E29") (pinfunction "GND_E29") (pintype "passive"))
      (node (ref "P15") (pin "E32") (pinfunction "GND_E32") (pintype "passive"))
      (node (ref "P15") (pin "E35") (pinfunction "GND_E35") (pintype "passive"))
      (node (ref "P15") (pin "E38") (pinfunction "GND_E38") (pintype "passive"))
      (node (ref "P15") (pin "E4") (pinfunction "GND_E4") (pintype "passive"))
      (node (ref "P15") (pin "E40") (pinfunction "GND_E40") (pintype "passive"))
      (node (ref "P15") (pin "E5") (pinfunction "GND_E5") (pintype "passive"))
      (node (ref "P15") (pin "E8") (pinfunction "GND_E8") (pintype "passive"))
      (node (ref "P15") (pin "F12") (pinfunction "GND_F12") (pintype "passive"))
      (node (ref "P15") (pin "F15") (pinfunction "GND_F15") (pintype "passive"))
      (node (ref "P15") (pin "F18") (pinfunction "GND_F18") (pintype "passive"))
      (node (ref "P15") (pin "F2") (pinfunction "GND_F2") (pintype "passive"))
      (node (ref "P15") (pin "F21") (pinfunction "GND_F21") (pintype "passive"))
      (node (ref "P15") (pin "F24") (pinfunction "GND_F24") (pintype "passive"))
      (node (ref "P15") (pin "F27") (pinfunction "GND_F27") (pintype "passive"))
      (node (ref "P15") (pin "F3") (pinfunction "GND_F3") (pintype "passive"))
      (node (ref "P15") (pin "F30") (pinfunction "GND_F30") (pintype "passive"))
      (node (ref "P15") (pin "F33") (pinfunction "GND_F33") (pintype "passive"))
      (node (ref "P15") (pin "F36") (pinfunction "GND_F36") (pintype "passive"))
      (node (ref "P15") (pin "F39") (pinfunction "GND_F39") (pintype "passive"))
      (node (ref "P15") (pin "F6") (pinfunction "GND_F6") (pintype "passive"))
      (node (ref "P15") (pin "F9") (pinfunction "GND_F9") (pintype "passive"))
      (node (ref "P15") (pin "G1") (pinfunction "GND_G1") (pintype "passive"))
      (node (ref "P15") (pin "G11") (pinfunction "GND_G11") (pintype "passive"))
      (node (ref "P15") (pin "G14") (pinfunction "GND_G14") (pintype "passive"))
      (node (ref "P15") (pin "G17") (pinfunction "GND_G17") (pintype "passive"))
      (node (ref "P15") (pin "G20") (pinfunction "GND_G20") (pintype "passive"))
      (node (ref "P15") (pin "G23") (pinfunction "GND_G23") (pintype "passive"))
      (node (ref "P15") (pin "G26") (pinfunction "GND_G26") (pintype "passive"))
      (node (ref "P15") (pin "G29") (pinfunction "GND_G29") (pintype "passive"))
      (node (ref "P15") (pin "G32") (pinfunction "GND_G32") (pintype "passive"))
      (node (ref "P15") (pin "G35") (pinfunction "GND_G35") (pintype "passive"))
      (node (ref "P15") (pin "G38") (pinfunction "GND_G38") (pintype "passive"))
      (node (ref "P15") (pin "G4") (pinfunction "GND_G4") (pintype "passive"))
      (node (ref "P15") (pin "G40") (pinfunction "GND_G40") (pintype "passive"))
      (node (ref "P15") (pin "G5") (pinfunction "GND_G5") (pintype "passive"))
      (node (ref "P15") (pin "G8") (pinfunction "GND_G8") (pintype "passive"))
      (node (ref "P15") (pin "H12") (pinfunction "GND_H12") (pintype "passive"))
      (node (ref "P15") (pin "H15") (pinfunction "GND_H15") (pintype "passive"))
      (node (ref "P15") (pin "H18") (pinfunction "GND_H18") (pintype "passive"))
      (node (ref "P15") (pin "H21") (pinfunction "GND_H21") (pintype "passive"))
      (node (ref "P15") (pin "H24") (pinfunction "GND_H24") (pintype "passive"))
      (node (ref "P15") (pin "H27") (pinfunction "GND_H27") (pintype "passive"))
      (node (ref "P15") (pin "H3") (pinfunction "GND_H3") (pintype "passive"))
      (node (ref "P15") (pin "H30") (pinfunction "GND_H30") (pintype "passive"))
      (node (ref "P15") (pin "H33") (pinfunction "GND_H33") (pintype "passive"))
      (node (ref "P15") (pin "H36") (pinfunction "GND_H36") (pintype "passive"))
      (node (ref "P15") (pin "H39") (pinfunction "GND_H39") (pintype "passive"))
      (node (ref "P15") (pin "H6") (pinfunction "GND_H6") (pintype "passive"))
      (node (ref "P15") (pin "H9") (pinfunction "GND_H9") (pintype "passive"))
      (node (ref "P15") (pin "J1") (pinfunction "GND_J1") (pintype "passive"))
      (node (ref "P15") (pin "J11") (pinfunction "GND_J11") (pintype "passive"))
      (node (ref "P15") (pin "J14") (pinfunction "GND_J14") (pintype "passive"))
      (node (ref "P15") (pin "J17") (pinfunction "GND_J17") (pintype "passive"))
      (node (ref "P15") (pin "J20") (pinfunction "GND_J20") (pintype "passive"))
      (node (ref "P15") (pin "J23") (pinfunction "GND_J23") (pintype "passive"))
      (node (ref "P15") (pin "J26") (pinfunction "GND_J26") (pintype "passive"))
      (node (ref "P15") (pin "J29") (pinfunction "GND_J29") (pintype "passive"))
      (node (ref "P15") (pin "J32") (pinfunction "GND_J32") (pintype "passive"))
      (node (ref "P15") (pin "J35") (pinfunction "GND_J35") (pintype "passive"))
      (node (ref "P15") (pin "J38") (pinfunction "GND_J38") (pintype "passive"))
      (node (ref "P15") (pin "J4") (pinfunction "GND_J4") (pintype "passive"))
      (node (ref "P15") (pin "J40") (pinfunction "GND_J40") (pintype "passive"))
      (node (ref "P15") (pin "J5") (pinfunction "GND_J5") (pintype "passive"))
      (node (ref "P15") (pin "J8") (pinfunction "GND_J8") (pintype "passive"))
      (node (ref "P15") (pin "K12") (pinfunction "GND_K12") (pintype "passive"))
      (node (ref "P15") (pin "K15") (pinfunction "GND_K15") (pintype "passive"))
      (node (ref "P15") (pin "K18") (pinfunction "GND_K18") (pintype "passive"))
      (node (ref "P15") (pin "K2") (pinfunction "GND_K2") (pintype "passive"))
      (node (ref "P15") (pin "K21") (pinfunction "GND_K21") (pintype "passive"))
      (node (ref "P15") (pin "K24") (pinfunction "GND_K24") (pintype "passive"))
      (node (ref "P15") (pin "K27") (pinfunction "GND_K27") (pintype "passive"))
      (node (ref "P15") (pin "K3") (pinfunction "GND_K3") (pintype "passive"))
      (node (ref "P15") (pin "K30") (pinfunction "GND_K30") (pintype "passive"))
      (node (ref "P15") (pin "K33") (pinfunction "GND_K33") (pintype "passive"))
      (node (ref "P15") (pin "K36") (pinfunction "GND_K36") (pintype "passive"))
      (node (ref "P15") (pin "K39") (pinfunction "GND_K39") (pintype "passive"))
      (node (ref "P15") (pin "K6") (pinfunction "GND_K6") (pintype "passive"))
      (node (ref "P15") (pin "K9") (pinfunction "GND_K9") (pintype "passive"))
      (node (ref "Q12") (pin "2") (pinfunction "S_2") (pintype "passive"))
      (node (ref "R79") (pin "1") (pinfunction "1_1") (pintype "passive"))
      (node (ref "U25") (pin "3") (pinfunction "GND_3") (pintype "power_in"))
    )
    (net (code "215") (name "Net-(DS12-A)") (class "Default")
      (node (ref "DS12") (pin "1") (pinfunction "A_1") (pintype "passive"))
      (node (ref "R77") (pin "1") (pinfunction "1_1") (pintype "passive"))
    )
    (net (code "216") (name "Net-(DS12-K)") (class "Default")
      (node (ref "DS12") (pin "2") (pinfunction "K_2") (pintype "passive"))
      (node (ref "Q12") (pin "3") (pinfunction "D_3") (pintype "passive"))
    )
    (net (code "217") (name "Net-(Q12-G)") (class "Default")
      (node (ref "Q12") (pin "1") (pinfunction "G_1") (pintype "passive"))
      (node (ref "R78") (pin "2") (pinfunction "2_2") (pintype "passive"))
    )
    (net (code "218") (name "unconnected-(P15B-DP8_C2M_N-PadB29)") (class "Default")
      (node (ref "P15") (pin "B29") (pinfunction "DP8_C2M_N_B29") (pintype "passive+no_connect"))
    )
    (net (code "219") (name "unconnected-(P15B-DP8_C2M_P-PadB28)") (class "Default")
      (node (ref "P15") (pin "B28") (pinfunction "DP8_C2M_P_B28") (pintype "passive+no_connect"))
    )
    (net (code "220") (name "unconnected-(P15B-DP8_M2C_N-PadB9)") (class "Default")
      (node (ref "P15") (pin "B9") (pinfunction "DP8_M2C_N_B9") (pintype "passive+no_connect"))
    )
    (net (code "221") (name "unconnected-(P15B-DP8_M2C_P-PadB8)") (class "Default")
      (node (ref "P15") (pin "B8") (pinfunction "DP8_M2C_P_B8") (pintype "passive+no_connect"))
    )
    (net (code "222") (name "unconnected-(P15B-DP9_C2M_N-PadB25)") (class "Default")
      (node (ref "P15") (pin "B25") (pinfunction "DP9_C2M_N_B25") (pintype "passive+no_connect"))
    )
    (net (code "223") (name "unconnected-(P15B-DP9_C2M_P-PadB24)") (class "Default")
      (node (ref "P15") (pin "B24") (pinfunction "DP9_C2M_P_B24") (pintype "passive+no_connect"))
    )
    (net (code "224") (name "unconnected-(P15B-DP9_M2C_N-PadB5)") (class "Default")
      (node (ref "P15") (pin "B5") (pinfunction "DP9_M2C_N_B5") (pintype "passive+no_connect"))
    )
    (net (code "225") (name "unconnected-(P15B-DP9_M2C_P-PadB4)") (class "Default")
      (node (ref "P15") (pin "B4") (pinfunction "DP9_M2C_P_B4") (pintype "passive+no_connect"))
    )
    (net (code "226") (name "unconnected-(P15B-RES0-PadB40)") (class "Default")
      (node (ref "P15") (pin "B40") (pinfunction "RES0_B40") (pintype "passive+no_connect"))
    )
    (net (code "227") (name "unconnected-(P15B-RES1-PadB1)") (class "Default")
      (node (ref "P15") (pin "B1") (pinfunction "RES1_B1") (pintype "passive+no_connect"))
    )
    (net (code "228") (name "unconnected-(P15D-TCK-PadD29)") (class "Default")
      (node (ref "P15") (pin "D29") (pinfunction "TCK_D29") (pintype "passive+no_connect"))
    )
    (net (code "229") (name "unconnected-(P15D-TMS-PadD33)") (class "Default")
      (node (ref "P15") (pin "D33") (pinfunction "TMS_D33") (pintype "passive+no_connect"))
    )
    (net (code "230") (name "unconnected-(P15D-TRST_L-PadD34)") (class "Default")
      (node (ref "P15") (pin "D34") (pinfunction "TRST_L_D34") (pintype "passive+no_connect"))
    )
    (net (code "231") (name "unconnected-(P15E-HB19_N-PadE34)") (class "Default")
      (node (ref "P15") (pin "E34") (pinfunction "HB19_N_E34") (pintype "passive+no_connect"))
    )
    (net (code "232") (name "unconnected-(P15E-HB19_P-PadE33)") (class "Default")
      (node (ref "P15") (pin "E33") (pinfunction "HB19_P_E33") (pintype "passive+no_connect"))
    )
    (net (code "233") (name "unconnected-(P15E-HB21_N-PadE37)") (class "Default")
      (node (ref "P15") (pin "E37") (pinfunction "HB21_N_E37") (pintype "passive+no_connect"))
    )
    (net (code "234") (name "unconnected-(P15E-HB21_P-PadE36)") (class "Default")
      (node (ref "P15") (pin "E36") (pinfunction "HB21_P_E36") (pintype "passive+no_connect"))
    )
    (net (code "235") (name "unconnected-(P15E-VADJ-PadE39)") (class "Default")
      (node (ref "P15") (pin "E39") (pinfunction "VADJ_E39") (pintype "passive"))
    )
    (net (code "236") (name "unconnected-(P15F-HB16_N-PadF35)") (class "Default")
      (node (ref "P15") (pin "F35") (pinfunction "HB16_N_F35") (pintype "passive+no_connect"))
    )
    (net (code "237") (name "unconnected-(P15F-HB16_P-PadF34)") (class "Default")
      (node (ref "P15") (pin "F34") (pinfunction "HB16_P_F34") (pintype "passive+no_connect"))
    )
    (net (code "238") (name "unconnected-(P15F-HB20_N-PadF38)") (class "Default")
      (node (ref "P15") (pin "F38") (pinfunction "HB20_N_F38") (pintype "passive+no_connect"))
    )
    (net (code "239") (name "unconnected-(P15F-HB20_P-PadF37)") (class "Default")
      (node (ref "P15") (pin "F37") (pinfunction "HB20_P_F37") (pintype "passive+no_connect"))
    )
    (net (code "240") (name "unconnected-(P15F-VADJ-PadF40)") (class "Default")
      (node (ref "P15") (pin "F40") (pinfunction "VADJ_F40") (pintype "passive"))
    )
    (net (code "241") (name "unconnected-(P15G-VADJ-PadG39)") (class "Default")
      (node (ref "P15") (pin "G39") (pinfunction "VADJ_G39") (pintype "passive"))
    )
    (net (code "242") (name "unconnected-(P15H-VADJ-PadH40)") (class "Default")
      (node (ref "P15") (pin "H40") (pinfunction "VADJ_H40") (pintype "passive"))
    )
    (net (code "243") (name "unconnected-(P15H-VREF_A_M2C-PadH1)") (class "Default")
      (node (ref "P15") (pin "H1") (pinfunction "VREF_A_M2C_H1") (pintype "passive+no_connect"))
    )
    (net (code "244") (name "unconnected-(P15I-HB15_N-PadJ34)") (class "Default")
      (node (ref "P15") (pin "J34") (pinfunction "HB15_N_J34") (pintype "passive+no_connect"))
    )
    (net (code "245") (name "unconnected-(P15I-HB15_P-PadJ33)") (class "Default")
      (node (ref "P15") (pin "J33") (pinfunction "HB15_P_J33") (pintype "passive+no_connect"))
    )
    (net (code "246") (name "unconnected-(P15I-HB18_N-PadJ37)") (class "Default")
      (node (ref "P15") (pin "J37") (pinfunction "HB18_N_J37") (pintype "passive+no_connect"))
    )
    (net (code "247") (name "unconnected-(P15I-HB18_P-PadJ36)") (class "Default")
      (node (ref "P15") (pin "J36") (pinfunction "HB18_P_J36") (pintype "passive+no_connect"))
    )
    (net (code "248") (name "unconnected-(P15I-VIO_B_M2C-PadJ39)") (class "Default")
      (node (ref "P15") (pin "J39") (pinfunction "VIO_B_M2C_J39") (pintype "passive+no_connect"))
    )
    (net (code "249") (name "unconnected-(P15J-HB17_N_CC-PadK38)") (class "Default")
      (node (ref "P15") (pin "K38") (pinfunction "HB17_N_CC_K38") (pintype "passive+no_connect"))
    )
    (net (code "250") (name "unconnected-(P15J-HB17_P_CC-PadK37)") (class "Default")
      (node (ref "P15") (pin "K37") (pinfunction "HB17_P_CC_K37") (pintype "passive+no_connect"))
    )
    (net (code "251") (name "unconnected-(P15J-VIO_B_M2C-PadK40)") (class "Default")
      (node (ref "P15") (pin "K40") (pinfunction "VIO_B_M2C_K40") (pintype "passive+no_connect"))
    )
    (net (code "252") (name "unconnected-(P15J-VREF_B_M2C-PadK1)") (class "Default")
      (node (ref "P15") (pin "K1") (pinfunction "VREF_B_M2C_K1") (pintype "passive+no_connect"))
    )
  )
)
